# dabpi__v1.net
KiCad netlist of a schematic drawn in EAGLE
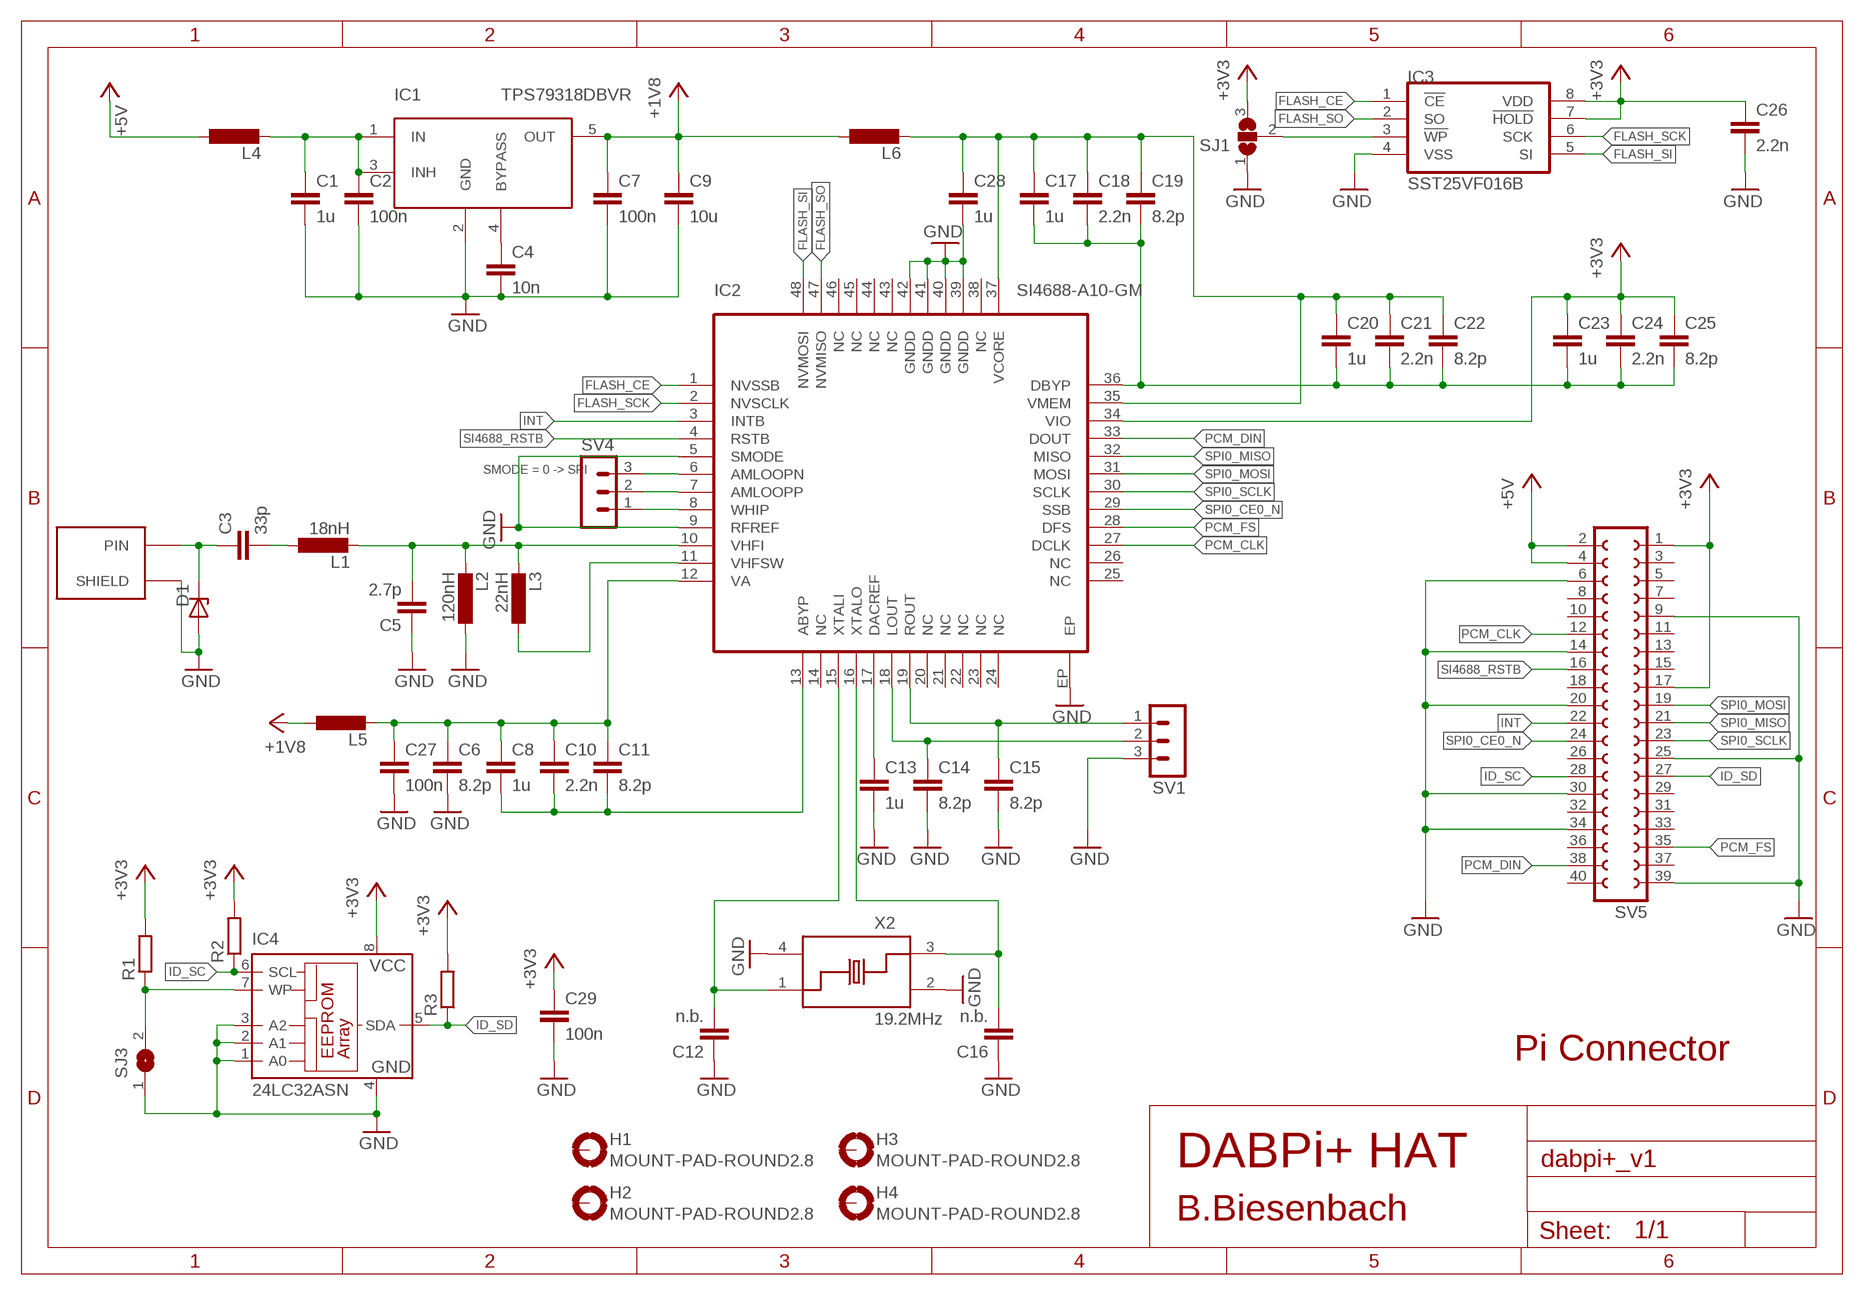
[diagram p0: schematic, sheet 1]

(export (version "E")
  (design (tool "Eeschema 10.0.6"))
  (components
    (comp (ref "C1")
      (value "1u")
      (footprint "eagle-import:SMD0603")
      (libsource (lib "eagle-import") (part "C0603"))
    )
    (comp (ref "C2")
      (value "100n")
      (footprint "eagle-import:SMD0603")
      (libsource (lib "eagle-import") (part "C0603"))
    )
    (comp (ref "C3")
      (value "33p")
      (footprint "eagle-import:SMD0402")
      (libsource (lib "eagle-import") (part "C0402"))
    )
    (comp (ref "C4")
      (value "10n")
      (footprint "eagle-import:SMD0603")
      (libsource (lib "eagle-import") (part "C0603"))
    )
    (comp (ref "C5")
      (value "2.7p")
      (footprint "eagle-import:SMD0402")
      (libsource (lib "eagle-import") (part "C0402"))
    )
    (comp (ref "C6")
      (value "8.2p")
      (footprint "eagle-import:SMD0603")
      (libsource (lib "eagle-import") (part "C0603"))
    )
    (comp (ref "C7")
      (value "100n")
      (footprint "eagle-import:SMD0603")
      (libsource (lib "eagle-import") (part "C0603"))
    )
    (comp (ref "C8")
      (value "1u")
      (footprint "eagle-import:SMD0603")
      (libsource (lib "eagle-import") (part "C0603"))
    )
    (comp (ref "C9")
      (value "10u")
      (footprint "eagle-import:SMD0603")
      (libsource (lib "eagle-import") (part "C0603"))
    )
    (comp (ref "C10")
      (value "2.2n")
      (footprint "eagle-import:SMD0603")
      (libsource (lib "eagle-import") (part "C0603"))
    )
    (comp (ref "C11")
      (value "8.2p")
      (footprint "eagle-import:SMD0603")
      (libsource (lib "eagle-import") (part "C0603"))
    )
    (comp (ref "C12")
      (value "n.b.")
      (footprint "eagle-import:SMD0402")
      (libsource (lib "eagle-import") (part "C0402"))
    )
    (comp (ref "C13")
      (value "1u")
      (footprint "eagle-import:SMD0603")
      (libsource (lib "eagle-import") (part "C0603"))
    )
    (comp (ref "C14")
      (value "8.2p")
      (footprint "eagle-import:SMD0603")
      (libsource (lib "eagle-import") (part "C0603"))
    )
    (comp (ref "C15")
      (value "8.2p")
      (footprint "eagle-import:SMD0603")
      (libsource (lib "eagle-import") (part "C0603"))
    )
    (comp (ref "C16")
      (value "n.b.")
      (footprint "eagle-import:SMD0402")
      (libsource (lib "eagle-import") (part "C0402"))
    )
    (comp (ref "C17")
      (value "1u")
      (footprint "eagle-import:SMD0603")
      (libsource (lib "eagle-import") (part "C0603"))
    )
    (comp (ref "C18")
      (value "2.2n")
      (footprint "eagle-import:SMD0603")
      (libsource (lib "eagle-import") (part "C0603"))
    )
    (comp (ref "C19")
      (value "8.2p")
      (footprint "eagle-import:SMD0603")
      (libsource (lib "eagle-import") (part "C0603"))
    )
    (comp (ref "C20")
      (value "1u")
      (footprint "eagle-import:SMD0603")
      (libsource (lib "eagle-import") (part "C0603"))
    )
    (comp (ref "C21")
      (value "2.2n")
      (footprint "eagle-import:SMD0603")
      (libsource (lib "eagle-import") (part "C0603"))
    )
    (comp (ref "C22")
      (value "8.2p")
      (footprint "eagle-import:SMD0603")
      (libsource (lib "eagle-import") (part "C0603"))
    )
    (comp (ref "C23")
      (value "1u")
      (footprint "eagle-import:SMD0603")
      (libsource (lib "eagle-import") (part "C0603"))
    )
    (comp (ref "C24")
      (value "2.2n")
      (footprint "eagle-import:SMD0603")
      (libsource (lib "eagle-import") (part "C0603"))
    )
    (comp (ref "C25")
      (value "8.2p")
      (footprint "eagle-import:SMD0603")
      (libsource (lib "eagle-import") (part "C0603"))
    )
    (comp (ref "C26")
      (value "2.2n")
      (footprint "eagle-import:SMD0603")
      (libsource (lib "eagle-import") (part "C0603"))
    )
    (comp (ref "C27")
      (value "100n")
      (footprint "eagle-import:SMD0603")
      (libsource (lib "eagle-import") (part "C0603"))
    )
    (comp (ref "C28")
      (value "1u")
      (footprint "eagle-import:SMD0603")
      (libsource (lib "eagle-import") (part "C0603"))
    )
    (comp (ref "C29")
      (value "100n")
      (footprint "eagle-import:SMD0603")
      (libsource (lib "eagle-import") (part "C0603"))
    )
    (comp (ref "D1")
      (value "ESD9L5.0")
      (footprint "eagle-import:SOD923")
      (libsource (lib "eagle-import") (part "ESD9L5.0"))
    )
    (comp (ref "H1")
      (value "MOUNT-PAD-ROUND2.8")
      (footprint "eagle-import:2,8-PAD")
      (libsource (lib "eagle-import") (part "MOUNT-PAD-ROUND2.8"))
    )
    (comp (ref "H2")
      (value "MOUNT-PAD-ROUND2.8")
      (footprint "eagle-import:2,8-PAD")
      (libsource (lib "eagle-import") (part "MOUNT-PAD-ROUND2.8"))
    )
    (comp (ref "H3")
      (value "MOUNT-PAD-ROUND2.8")
      (footprint "eagle-import:2,8-PAD")
      (libsource (lib "eagle-import") (part "MOUNT-PAD-ROUND2.8"))
    )
    (comp (ref "H4")
      (value "MOUNT-PAD-ROUND2.8")
      (footprint "eagle-import:2,8-PAD")
      (libsource (lib "eagle-import") (part "MOUNT-PAD-ROUND2.8"))
    )
    (comp (ref "IC1")
      (value "TPS79318DBVR")
      (footprint "eagle-import:SOT23-5")
      (libsource (lib "eagle-import") (part "TPS79318DBVR"))
    )
    (comp (ref "IC2")
      (value "SI4688-A10-GM")
      (footprint "eagle-import:QFN48")
      (libsource (lib "eagle-import") (part "SI4688-A10-GM"))
    )
    (comp (ref "IC3")
      (value "SST25VF016B")
      (footprint "eagle-import:SO08")
      (libsource (lib "eagle-import") (part "SST25VF016B"))
    )
    (comp (ref "IC4")
      (value "24LC32ASN")
      (footprint "eagle-import:SO-08")
      (fields (field (name "MF") "MICROCHIP") (field (name "MPN") "24LC32A/SN"))
      (libsource (lib "eagle-import") (part "24SNLC32A"))
    )
    (comp (ref "L1")
      (value "18nH")
      (footprint "eagle-import:SMD0402")
      (libsource (lib "eagle-import") (part "L0402"))
    )
    (comp (ref "L2")
      (value "120nH")
      (footprint "eagle-import:SMD0402")
      (libsource (lib "eagle-import") (part "L0402"))
    )
    (comp (ref "L3")
      (value "22nH")
      (footprint "eagle-import:SMD0402")
      (libsource (lib "eagle-import") (part "L0402"))
    )
    (comp (ref "L4")
      (value "L0603")
      (footprint "eagle-import:SMD0603")
      (libsource (lib "eagle-import") (part "L0603"))
    )
    (comp (ref "L5")
      (value "L0603")
      (footprint "eagle-import:SMD0603")
      (libsource (lib "eagle-import") (part "L0603"))
    )
    (comp (ref "L6")
      (value "L0603")
      (footprint "eagle-import:SMD0603")
      (libsource (lib "eagle-import") (part "L0603"))
    )
    (comp (ref "R1")
      (value "R0603")
      (footprint "eagle-import:SMD0603")
      (libsource (lib "eagle-import") (part "R0603"))
    )
    (comp (ref "R2")
      (value "R0603")
      (footprint "eagle-import:SMD0603")
      (libsource (lib "eagle-import") (part "R0603"))
    )
    (comp (ref "R3")
      (value "R0603")
      (footprint "eagle-import:SMD0603")
      (libsource (lib "eagle-import") (part "R0603"))
    )
    (comp (ref "SJ1")
      (value "SJ2W")
      (footprint "eagle-import:SJ_2")
      (libsource (lib "eagle-import") (part "SJ2W"))
    )
    (comp (ref "SJ3") (value "SJ") (footprint "eagle-import:SJ") (libsource (lib "eagle-import") (part "SJ")))
    (comp (ref "SV1")
      (value "MA03-1")
      (footprint "eagle-import:MA03-1")
      (libsource (lib "eagle-import") (part "MA03-1"))
    )
    (comp (ref "SV4")
      (value "MA03-1")
      (footprint "eagle-import:MA03-1")
      (libsource (lib "eagle-import") (part "MA03-1"))
    )
    (comp (ref "SV5")
      (value "FE20-2")
      (footprint "eagle-import:FE20-2")
      (libsource (lib "eagle-import") (part "FE20-2"))
    )
    (comp (ref "X1")
      (value "SMA_LP_1.57MM")
      (footprint "eagle-import:SMA_LP_1.57MM")
      (libsource (lib "eagle-import") (part "SMA_LP_1.57MM"))
    )
    (comp (ref "X2")
      (value "19.2MHz")
      (footprint "eagle-import:XTAL_3.2X2.5")
      (libsource (lib "eagle-import") (part "XTAL_3.2X2.5"))
    )
  )
  (nets
    (net (code "1") (name "+1V8") (class "Default")
      (node (ref "C7") (pin "1") (pinfunction "1_1") (pintype "passive"))
      (node (ref "C9") (pin "1") (pinfunction "1_1") (pintype "passive"))
      (node (ref "IC1") (pin "5") (pinfunction "OUT_5") (pintype "power_in"))
      (node (ref "L5") (pin "1") (pinfunction "1_1") (pintype "passive"))
      (node (ref "L6") (pin "1") (pinfunction "1_1") (pintype "passive"))
    )
    (net (code "2") (name "+3V3") (class "Default")
      (node (ref "C23") (pin "1") (pinfunction "1_1") (pintype "passive"))
      (node (ref "C24") (pin "1") (pinfunction "1_1") (pintype "passive"))
      (node (ref "C25") (pin "1") (pinfunction "1_1") (pintype "passive"))
      (node (ref "C26") (pin "1") (pinfunction "1_1") (pintype "passive"))
      (node (ref "C29") (pin "1") (pinfunction "1_1") (pintype "passive"))
      (node (ref "IC2") (pin "34") (pinfunction "VIO_34") (pintype "power_in"))
      (node (ref "IC3") (pin "7") (pinfunction "~{HOLD}_7") (pintype "input"))
      (node (ref "IC3") (pin "8") (pinfunction "VDD_8") (pintype "power_in"))
      (node (ref "IC4") (pin "8") (pinfunction "VCC_8") (pintype "power_in"))
      (node (ref "R1") (pin "2") (pinfunction "2_2") (pintype "passive"))
      (node (ref "R2") (pin "2") (pinfunction "2_2") (pintype "passive"))
      (node (ref "R3") (pin "2") (pinfunction "2_2") (pintype "passive"))
      (node (ref "SJ1") (pin "3") (pinfunction "3_3") (pintype "passive"))
      (node (ref "SV5") (pin "1") (pinfunction "1_1") (pintype "passive"))
      (node (ref "SV5") (pin "17") (pinfunction "17_17") (pintype "passive"))
    )
    (net (code "3") (name "+5V") (class "Default")
      (node (ref "L4") (pin "1") (pinfunction "1_1") (pintype "passive"))
      (node (ref "SV5") (pin "2") (pinfunction "2_2") (pintype "passive"))
      (node (ref "SV5") (pin "4") (pinfunction "4_4") (pintype "passive"))
    )
    (net (code "4") (name "FLASH_CE") (class "Default")
      (node (ref "IC2") (pin "1") (pinfunction "NVSSB_1") (pintype "output"))
      (node (ref "IC3") (pin "1") (pinfunction "~{CE}_1") (pintype "input"))
    )
    (net (code "5") (name "FLASH_SCK") (class "Default")
      (node (ref "IC2") (pin "2") (pinfunction "NVSCLK_2") (pintype "output"))
      (node (ref "IC3") (pin "6") (pinfunction "SCK_6") (pintype "input"))
    )
    (net (code "6") (name "FLASH_SI") (class "Default")
      (node (ref "IC2") (pin "48") (pinfunction "NVMOSI_48") (pintype "output"))
      (node (ref "IC3") (pin "5") (pinfunction "SI_5") (pintype "input"))
    )
    (net (code "7") (name "FLASH_SO") (class "Default")
      (node (ref "IC2") (pin "47") (pinfunction "NVMISO_47") (pintype "input"))
      (node (ref "IC3") (pin "2") (pinfunction "SO_2") (pintype "output"))
    )
    (net (code "8") (name "GND") (class "Default")
      (node (ref "C1") (pin "2") (pinfunction "2_2") (pintype "passive"))
      (node (ref "C12") (pin "1") (pinfunction "1_1") (pintype "passive"))
      (node (ref "C13") (pin "2") (pinfunction "2_2") (pintype "passive"))
      (node (ref "C14") (pin "2") (pinfunction "2_2") (pintype "passive"))
      (node (ref "C15") (pin "2") (pinfunction "2_2") (pintype "passive"))
      (node (ref "C16") (pin "1") (pinfunction "1_1") (pintype "passive"))
      (node (ref "C2") (pin "2") (pinfunction "2_2") (pintype "passive"))
      (node (ref "C26") (pin "2") (pinfunction "2_2") (pintype "passive"))
      (node (ref "C27") (pin "2") (pinfunction "2_2") (pintype "passive"))
      (node (ref "C28") (pin "2") (pinfunction "2_2") (pintype "passive"))
      (node (ref "C29") (pin "2") (pinfunction "2_2") (pintype "passive"))
      (node (ref "C4") (pin "2") (pinfunction "2_2") (pintype "passive"))
      (node (ref "C5") (pin "1") (pinfunction "1_1") (pintype "passive"))
      (node (ref "C6") (pin "2") (pinfunction "2_2") (pintype "passive"))
      (node (ref "C7") (pin "2") (pinfunction "2_2") (pintype "passive"))
      (node (ref "C9") (pin "2") (pinfunction "2_2") (pintype "passive"))
      (node (ref "D1") (pin "A") (pinfunction "A_A") (pintype "passive"))
      (node (ref "IC1") (pin "2") (pinfunction "GND_2") (pintype "power_in"))
      (node (ref "IC2") (pin "39") (pinfunction "GNDD_39") (pintype "power_in"))
      (node (ref "IC2") (pin "40") (pinfunction "GNDD_40") (pintype "power_in"))
      (node (ref "IC2") (pin "41") (pinfunction "GNDD_41") (pintype "power_in"))
      (node (ref "IC2") (pin "42") (pinfunction "GNDD_42") (pintype "power_in"))
      (node (ref "IC2") (pin "5") (pinfunction "SMODE_5") (pintype "input"))
      (node (ref "IC2") (pin "9") (pinfunction "RFREF_9") (pintype "power_in"))
      (node (ref "IC2") (pin "EP") (pinfunction "EP_EP") (pintype "bidirectional"))
      (node (ref "IC3") (pin "4") (pinfunction "VSS_4") (pintype "power_in"))
      (node (ref "IC4") (pin "1") (pinfunction "A0_1") (pintype "input"))
      (node (ref "IC4") (pin "2") (pinfunction "A1_2") (pintype "input"))
      (node (ref "IC4") (pin "3") (pinfunction "A2_3") (pintype "input"))
      (node (ref "IC4") (pin "4") (pinfunction "GND_4") (pintype "power_in"))
      (node (ref "L2") (pin "1") (pinfunction "1_1") (pintype "passive"))
      (node (ref "SJ1") (pin "1") (pinfunction "1_1") (pintype "passive"))
      (node (ref "SJ3") (pin "1") (pinfunction "1_1") (pintype "passive"))
      (node (ref "SV1") (pin "3") (pinfunction "3_3") (pintype "passive"))
      (node (ref "SV5") (pin "14") (pinfunction "14_14") (pintype "passive"))
      (node (ref "SV5") (pin "20") (pinfunction "20_20") (pintype "passive"))
      (node (ref "SV5") (pin "25") (pinfunction "25_25") (pintype "passive"))
      (node (ref "SV5") (pin "30") (pinfunction "30_30") (pintype "passive"))
      (node (ref "SV5") (pin "34") (pinfunction "34_34") (pintype "passive"))
      (node (ref "SV5") (pin "39") (pinfunction "39_39") (pintype "passive"))
      (node (ref "SV5") (pin "6") (pinfunction "6_6") (pintype "passive"))
      (node (ref "SV5") (pin "9") (pinfunction "9_9") (pintype "passive"))
      (node (ref "X1") (pin "GND") (pinfunction "SHIELD_GND") (pintype "power_in"))
      (node (ref "X1") (pin "GND@1") (pinfunction "SHIELD_GND@1") (pintype "power_in"))
      (node (ref "X1") (pin "GND@2") (pinfunction "SHIELD_GND@2") (pintype "power_in"))
      (node (ref "X1") (pin "GND@3") (pinfunction "SHIELD_GND@3") (pintype "power_in"))
      (node (ref "X2") (pin "2") (pinfunction "GND_2") (pintype "power_in"))
      (node (ref "X2") (pin "4") (pinfunction "GND_4") (pintype "power_in"))
    )
    (net (code "9") (name "ID_SC") (class "Default")
      (node (ref "IC4") (pin "6") (pinfunction "SCL_6") (pintype "input"))
      (node (ref "R2") (pin "1") (pinfunction "1_1") (pintype "passive"))
      (node (ref "SV5") (pin "28") (pinfunction "28_28") (pintype "passive"))
    )
    (net (code "10") (name "ID_SD") (class "Default")
      (node (ref "IC4") (pin "5") (pinfunction "SDA_5") (pintype "bidirectional"))
      (node (ref "R3") (pin "1") (pinfunction "1_1") (pintype "passive"))
      (node (ref "SV5") (pin "27") (pinfunction "27_27") (pintype "passive"))
    )
    (net (code "11") (name "INT") (class "Default")
      (node (ref "IC2") (pin "3") (pinfunction "INTB_3") (pintype "output"))
      (node (ref "SV5") (pin "22") (pinfunction "22_22") (pintype "passive"))
    )
    (net (code "12") (name "Net-(C3-Pad2)") (class "Default")
      (node (ref "C3") (pin "2") (pinfunction "2_2") (pintype "passive"))
      (node (ref "L1") (pin "1") (pinfunction "1_1") (pintype "passive"))
    )
    (net (code "13") (name "Net-(D1-C)") (class "Default")
      (node (ref "C3") (pin "1") (pinfunction "1_1") (pintype "passive"))
      (node (ref "D1") (pin "K") (pinfunction "C_K") (pintype "passive"))
      (node (ref "X1") (pin "PIN") (pinfunction "PIN_PIN") (pintype "passive"))
    )
    (net (code "14") (name "Net-(IC1-BYPASS)") (class "Default")
      (node (ref "C4") (pin "1") (pinfunction "1_1") (pintype "passive"))
      (node (ref "IC1") (pin "4") (pinfunction "BYPASS_4") (pintype "power_in"))
    )
    (net (code "15") (name "Net-(IC1-IN)") (class "Default")
      (node (ref "C1") (pin "1") (pinfunction "1_1") (pintype "passive"))
      (node (ref "C2") (pin "1") (pinfunction "1_1") (pintype "passive"))
      (node (ref "IC1") (pin "1") (pinfunction "IN_1") (pintype "power_in"))
      (node (ref "IC1") (pin "3") (pinfunction "INH_3") (pintype "input"))
      (node (ref "L4") (pin "2") (pinfunction "2_2") (pintype "passive"))
    )
    (net (code "16") (name "Net-(IC2-ABYP)") (class "Default")
      (node (ref "C10") (pin "2") (pinfunction "2_2") (pintype "passive"))
      (node (ref "C11") (pin "2") (pinfunction "2_2") (pintype "passive"))
      (node (ref "C8") (pin "2") (pinfunction "2_2") (pintype "passive"))
      (node (ref "IC2") (pin "13") (pinfunction "ABYP_13") (pintype "power_in"))
    )
    (net (code "17") (name "Net-(IC2-AMLOOPN)") (class "Default")
      (node (ref "IC2") (pin "6") (pinfunction "AMLOOPN_6") (pintype "power_in"))
      (node (ref "SV4") (pin "3") (pinfunction "3_3") (pintype "passive"))
    )
    (net (code "18") (name "Net-(IC2-AMLOOPP)") (class "Default")
      (node (ref "IC2") (pin "7") (pinfunction "AMLOOPP_7") (pintype "power_in"))
      (node (ref "SV4") (pin "2") (pinfunction "2_2") (pintype "passive"))
    )
    (net (code "19") (name "Net-(IC2-DACREF)") (class "Default")
      (node (ref "C13") (pin "1") (pinfunction "1_1") (pintype "passive"))
      (node (ref "IC2") (pin "17") (pinfunction "DACREF_17") (pintype "power_in"))
    )
    (net (code "20") (name "Net-(IC2-DBYP)") (class "Default")
      (node (ref "C17") (pin "2") (pinfunction "2_2") (pintype "passive"))
      (node (ref "C18") (pin "2") (pinfunction "2_2") (pintype "passive"))
      (node (ref "C19") (pin "2") (pinfunction "2_2") (pintype "passive"))
      (node (ref "C20") (pin "2") (pinfunction "2_2") (pintype "passive"))
      (node (ref "C21") (pin "2") (pinfunction "2_2") (pintype "passive"))
      (node (ref "C22") (pin "2") (pinfunction "2_2") (pintype "passive"))
      (node (ref "C23") (pin "2") (pinfunction "2_2") (pintype "passive"))
      (node (ref "C24") (pin "2") (pinfunction "2_2") (pintype "passive"))
      (node (ref "C25") (pin "2") (pinfunction "2_2") (pintype "passive"))
      (node (ref "IC2") (pin "36") (pinfunction "DBYP_36") (pintype "power_in"))
    )
    (net (code "21") (name "Net-(IC2-LOUT)") (class "Default")
      (node (ref "C14") (pin "1") (pinfunction "1_1") (pintype "passive"))
      (node (ref "IC2") (pin "18") (pinfunction "LOUT_18") (pintype "output"))
      (node (ref "SV1") (pin "2") (pinfunction "2_2") (pintype "passive"))
    )
    (net (code "22") (name "Net-(IC2-ROUT)") (class "Default")
      (node (ref "C15") (pin "1") (pinfunction "1_1") (pintype "passive"))
      (node (ref "IC2") (pin "19") (pinfunction "ROUT_19") (pintype "output"))
      (node (ref "SV1") (pin "1") (pinfunction "1_1") (pintype "passive"))
    )
    (net (code "23") (name "Net-(IC2-VA)") (class "Default")
      (node (ref "C10") (pin "1") (pinfunction "1_1") (pintype "passive"))
      (node (ref "C11") (pin "1") (pinfunction "1_1") (pintype "passive"))
      (node (ref "C27") (pin "1") (pinfunction "1_1") (pintype "passive"))
      (node (ref "C6") (pin "1") (pinfunction "1_1") (pintype "passive"))
      (node (ref "C8") (pin "1") (pinfunction "1_1") (pintype "passive"))
      (node (ref "IC2") (pin "12") (pinfunction "VA_12") (pintype "power_in"))
      (node (ref "L5") (pin "2") (pinfunction "2_2") (pintype "passive"))
    )
    (net (code "24") (name "Net-(IC2-VCORE)") (class "Default")
      (node (ref "C17") (pin "1") (pinfunction "1_1") (pintype "passive"))
      (node (ref "C18") (pin "1") (pinfunction "1_1") (pintype "passive"))
      (node (ref "C19") (pin "1") (pinfunction "1_1") (pintype "passive"))
      (node (ref "C20") (pin "1") (pinfunction "1_1") (pintype "passive"))
      (node (ref "C21") (pin "1") (pinfunction "1_1") (pintype "passive"))
      (node (ref "C22") (pin "1") (pinfunction "1_1") (pintype "passive"))
      (node (ref "C28") (pin "1") (pinfunction "1_1") (pintype "passive"))
      (node (ref "IC2") (pin "35") (pinfunction "VMEM_35") (pintype "power_in"))
      (node (ref "IC2") (pin "37") (pinfunction "VCORE_37") (pintype "power_in"))
      (node (ref "L6") (pin "2") (pinfunction "2_2") (pintype "passive"))
    )
    (net (code "25") (name "Net-(IC2-VHFI)") (class "Default")
      (node (ref "C5") (pin "2") (pinfunction "2_2") (pintype "passive"))
      (node (ref "IC2") (pin "10") (pinfunction "VHFI_10") (pintype "input"))
      (node (ref "L1") (pin "2") (pinfunction "2_2") (pintype "passive"))
      (node (ref "L2") (pin "2") (pinfunction "2_2") (pintype "passive"))
      (node (ref "L3") (pin "2") (pinfunction "2_2") (pintype "passive"))
    )
    (net (code "26") (name "Net-(IC2-VHFSW)") (class "Default")
      (node (ref "IC2") (pin "11") (pinfunction "VHFSW_11") (pintype "output"))
      (node (ref "L3") (pin "1") (pinfunction "1_1") (pintype "passive"))
    )
    (net (code "27") (name "Net-(IC2-WHIP)") (class "Default")
      (node (ref "IC2") (pin "8") (pinfunction "WHIP_8") (pintype "power_in"))
      (node (ref "SV4") (pin "1") (pinfunction "1_1") (pintype "passive"))
    )
    (net (code "28") (name "Net-(IC2-XTALI)") (class "Default")
      (node (ref "C12") (pin "2") (pinfunction "2_2") (pintype "passive"))
      (node (ref "IC2") (pin "15") (pinfunction "XTALI_15") (pintype "input"))
      (node (ref "X2") (pin "1") (pinfunction "1_1") (pintype "passive"))
    )
    (net (code "29") (name "Net-(IC2-XTALO)") (class "Default")
      (node (ref "C16") (pin "2") (pinfunction "2_2") (pintype "passive"))
      (node (ref "IC2") (pin "16") (pinfunction "XTALO_16") (pintype "output"))
      (node (ref "X2") (pin "3") (pinfunction "3_3") (pintype "passive"))
    )
    (net (code "30") (name "Net-(IC3-~{WP})") (class "Default")
      (node (ref "IC3") (pin "3") (pinfunction "~{WP}_3") (pintype "input"))
      (node (ref "SJ1") (pin "2") (pinfunction "2_2") (pintype "passive"))
    )
    (net (code "31") (name "Net-(IC4-WP)") (class "Default")
      (node (ref "IC4") (pin "7") (pinfunction "WP_7") (pintype "input"))
      (node (ref "R1") (pin "1") (pinfunction "1_1") (pintype "passive"))
      (node (ref "SJ3") (pin "2") (pinfunction "2_2") (pintype "passive"))
    )
    (net (code "32") (name "PCM_CLK") (class "Default")
      (node (ref "IC2") (pin "27") (pinfunction "DCLK_27") (pintype "bidirectional"))
      (node (ref "SV5") (pin "12") (pinfunction "12_12") (pintype "passive"))
    )
    (net (code "33") (name "PCM_DIN") (class "Default")
      (node (ref "IC2") (pin "33") (pinfunction "DOUT_33") (pintype "output"))
      (node (ref "SV5") (pin "38") (pinfunction "38_38") (pintype "passive"))
    )
    (net (code "34") (name "PCM_FS") (class "Default")
      (node (ref "IC2") (pin "28") (pinfunction "DFS_28") (pintype "bidirectional"))
      (node (ref "SV5") (pin "35") (pinfunction "35_35") (pintype "passive"))
    )
    (net (code "35") (name "SI4688_RSTB") (class "Default")
      (node (ref "IC2") (pin "4") (pinfunction "RSTB_4") (pintype "input"))
      (node (ref "SV5") (pin "16") (pinfunction "16_16") (pintype "passive"))
    )
    (net (code "36") (name "SPI0_CE0_N") (class "Default")
      (node (ref "IC2") (pin "29") (pinfunction "SSB_29") (pintype "input"))
      (node (ref "SV5") (pin "24") (pinfunction "24_24") (pintype "passive"))
    )
    (net (code "37") (name "SPI0_MISO") (class "Default")
      (node (ref "IC2") (pin "32") (pinfunction "MISO_32") (pintype "bidirectional"))
      (node (ref "SV5") (pin "21") (pinfunction "21_21") (pintype "passive"))
    )
    (net (code "38") (name "SPI0_MOSI") (class "Default")
      (node (ref "IC2") (pin "31") (pinfunction "MOSI_31") (pintype "bidirectional"))
      (node (ref "SV5") (pin "19") (pinfunction "19_19") (pintype "passive"))
    )
    (net (code "39") (name "SPI0_SCLK") (class "Default")
      (node (ref "IC2") (pin "30") (pinfunction "SCLK_30") (pintype "input"))
      (node (ref "SV5") (pin "23") (pinfunction "23_23") (pintype "passive"))
    )
    (net (code "40") (name "unconnected-(H1-MOUNT-PadB2,8)") (class "Default")
      (node (ref "H1") (pin "B2,8") (pinfunction "MOUNT_B2,8") (pintype "passive"))
    )
    (net (code "41") (name "unconnected-(H2-MOUNT-PadB2,8)") (class "Default")
      (node (ref "H2") (pin "B2,8") (pinfunction "MOUNT_B2,8") (pintype "passive"))
    )
    (net (code "42") (name "unconnected-(H3-MOUNT-PadB2,8)") (class "Default")
      (node (ref "H3") (pin "B2,8") (pinfunction "MOUNT_B2,8") (pintype "passive"))
    )
    (net (code "43") (name "unconnected-(H4-MOUNT-PadB2,8)") (class "Default")
      (node (ref "H4") (pin "B2,8") (pinfunction "MOUNT_B2,8") (pintype "passive"))
    )
    (net (code "44") (name "unconnected-(IC2-NC-Pad14)") (class "Default")
      (node (ref "IC2") (pin "14") (pinfunction "NC_14") (pintype "no_connect"))
    )
    (net (code "45") (name "unconnected-(IC2-NC-Pad20)") (class "Default")
      (node (ref "IC2") (pin "20") (pinfunction "NC_20") (pintype "no_connect"))
    )
    (net (code "46") (name "unconnected-(IC2-NC-Pad21)") (class "Default")
      (node (ref "IC2") (pin "21") (pinfunction "NC_21") (pintype "no_connect"))
    )
    (net (code "47") (name "unconnected-(IC2-NC-Pad22)") (class "Default")
      (node (ref "IC2") (pin "22") (pinfunction "NC_22") (pintype "no_connect"))
    )
    (net (code "48") (name "unconnected-(IC2-NC-Pad23)") (class "Default")
      (node (ref "IC2") (pin "23") (pinfunction "NC_23") (pintype "no_connect"))
    )
    (net (code "49") (name "unconnected-(IC2-NC-Pad24)") (class "Default")
      (node (ref "IC2") (pin "24") (pinfunction "NC_24") (pintype "no_connect"))
    )
    (net (code "50") (name "unconnected-(IC2-NC-Pad25)") (class "Default")
      (node (ref "IC2") (pin "25") (pinfunction "NC_25") (pintype "no_connect"))
    )
    (net (code "51") (name "unconnected-(IC2-NC-Pad26)") (class "Default")
      (node (ref "IC2") (pin "26") (pinfunction "NC_26") (pintype "no_connect"))
    )
    (net (code "52") (name "unconnected-(IC2-NC-Pad38)") (class "Default")
      (node (ref "IC2") (pin "38") (pinfunction "NC_38") (pintype "no_connect"))
    )
    (net (code "53") (name "unconnected-(IC2-NC-Pad43)") (class "Default")
      (node (ref "IC2") (pin "43") (pinfunction "NC_43") (pintype "no_connect"))
    )
    (net (code "54") (name "unconnected-(IC2-NC-Pad44)") (class "Default")
      (node (ref "IC2") (pin "44") (pinfunction "NC_44") (pintype "no_connect"))
    )
    (net (code "55") (name "unconnected-(IC2-NC-Pad45)") (class "Default")
      (node (ref "IC2") (pin "45") (pinfunction "NC_45") (pintype "no_connect"))
    )
    (net (code "56") (name "unconnected-(IC2-NC-Pad46)") (class "Default")
      (node (ref "IC2") (pin "46") (pinfunction "NC_46") (pintype "no_connect"))
    )
    (net (code "57") (name "unconnected-(SV5-Pad3)") (class "Default")
      (node (ref "SV5") (pin "3") (pinfunction "3_3") (pintype "passive"))
    )
    (net (code "58") (name "unconnected-(SV5-Pad5)") (class "Default")
      (node (ref "SV5") (pin "5") (pinfunction "5_5") (pintype "passive"))
    )
    (net (code "59") (name "unconnected-(SV5-Pad7)") (class "Default")
      (node (ref "SV5") (pin "7") (pinfunction "7_7") (pintype "passive"))
    )
    (net (code "60") (name "unconnected-(SV5-Pad8)") (class "Default")
      (node (ref "SV5") (pin "8") (pinfunction "8_8") (pintype "passive"))
    )
    (net (code "61") (name "unconnected-(SV5-Pad10)") (class "Default")
      (node (ref "SV5") (pin "10") (pinfunction "10_10") (pintype "passive"))
    )
    (net (code "62") (name "unconnected-(SV5-Pad11)") (class "Default")
      (node (ref "SV5") (pin "11") (pinfunction "11_11") (pintype "passive"))
    )
    (net (code "63") (name "unconnected-(SV5-Pad13)") (class "Default")
      (node (ref "SV5") (pin "13") (pinfunction "13_13") (pintype "passive"))
    )
    (net (code "64") (name "unconnected-(SV5-Pad15)") (class "Default")
      (node (ref "SV5") (pin "15") (pinfunction "15_15") (pintype "passive"))
    )
    (net (code "65") (name "unconnected-(SV5-Pad18)") (class "Default")
      (node (ref "SV5") (pin "18") (pinfunction "18_18") (pintype "passive"))
    )
    (net (code "66") (name "unconnected-(SV5-Pad26)") (class "Default")
      (node (ref "SV5") (pin "26") (pinfunction "26_26") (pintype "passive"))
    )
    (net (code "67") (name "unconnected-(SV5-Pad29)") (class "Default")
      (node (ref "SV5") (pin "29") (pinfunction "29_29") (pintype "passive"))
    )
    (net (code "68") (name "unconnected-(SV5-Pad31)") (class "Default")
      (node (ref "SV5") (pin "31") (pinfunction "31_31") (pintype "passive"))
    )
    (net (code "69") (name "unconnected-(SV5-Pad32)") (class "Default")
      (node (ref "SV5") (pin "32") (pinfunction "32_32") (pintype "passive"))
    )
    (net (code "70") (name "unconnected-(SV5-Pad33)") (class "Default")
      (node (ref "SV5") (pin "33") (pinfunction "33_33") (pintype "passive"))
    )
    (net (code "71") (name "unconnected-(SV5-Pad36)") (class "Default")
      (node (ref "SV5") (pin "36") (pinfunction "36_36") (pintype "passive"))
    )
    (net (code "72") (name "unconnected-(SV5-Pad37)") (class "Default")
      (node (ref "SV5") (pin "37") (pinfunction "37_37") (pintype "passive"))
    )
    (net (code "73") (name "unconnected-(SV5-Pad40)") (class "Default")
      (node (ref "SV5") (pin "40") (pinfunction "40_40") (pintype "passive"))
    )
  )
)
